# 4out_6A_TS_v0_1.net
KiCad netlist of a schematic drawn in EAGLE
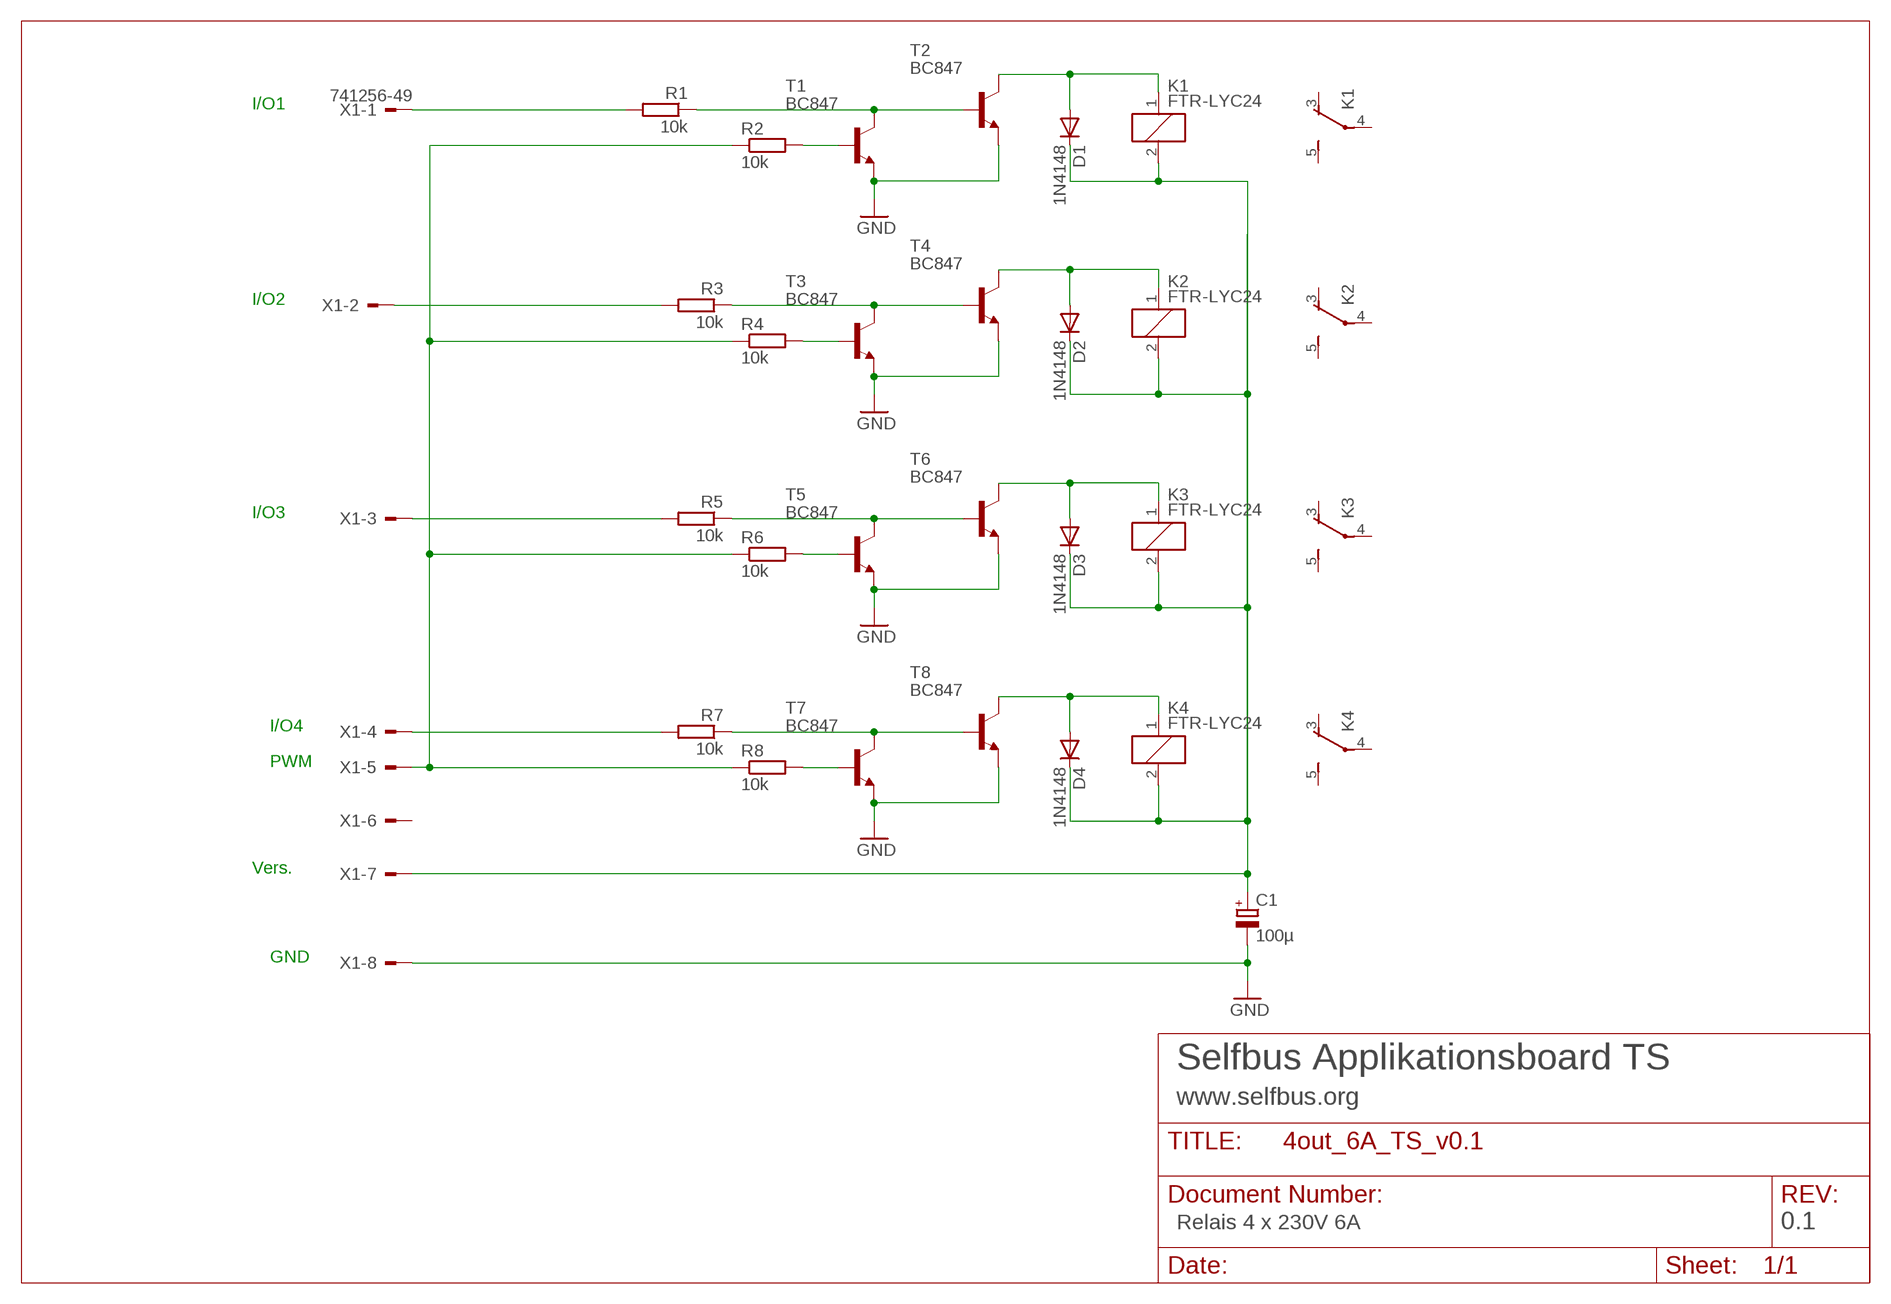
[diagram p0: schematic, sheet 1]

(export (version "E")
  (design (tool "Eeschema 10.0.6"))
  (components
    (comp (ref "C1")
      (value "100µ")
      (footprint "eagle-import:E2,5-6")
      (libsource (lib "eagle-import") (part "CPOL-EUE2.5-6"))
    )
    (comp (ref "D1")
      (value "1N4148")
      (footprint "eagle-import:MINIMELF")
      (libsource (lib "eagle-import") (part "DIODE-MINIMELF"))
    )
    (comp (ref "D2")
      (value "1N4148")
      (footprint "eagle-import:MINIMELF")
      (libsource (lib "eagle-import") (part "DIODE-MINIMELF"))
    )
    (comp (ref "D3")
      (value "1N4148")
      (footprint "eagle-import:MINIMELF")
      (libsource (lib "eagle-import") (part "DIODE-MINIMELF"))
    )
    (comp (ref "D4")
      (value "1N4148")
      (footprint "eagle-import:MINIMELF")
      (libsource (lib "eagle-import") (part "DIODE-MINIMELF"))
    )
    (comp (ref "K1")
      (value "FTR-LYC24")
      (footprint "eagle-import:FTR-LYC")
      (libsource (lib "eagle-import") (part "FTR-LYC24"))
    )
    (comp (ref "K2")
      (value "FTR-LYC24")
      (footprint "eagle-import:FTR-LYC")
      (libsource (lib "eagle-import") (part "FTR-LYC24"))
    )
    (comp (ref "K3")
      (value "FTR-LYC24")
      (footprint "eagle-import:FTR-LYC")
      (libsource (lib "eagle-import") (part "FTR-LYC24"))
    )
    (comp (ref "K4")
      (value "FTR-LYC24")
      (footprint "eagle-import:FTR-LYC")
      (libsource (lib "eagle-import") (part "FTR-LYC24"))
    )
    (comp (ref "R1")
      (value "10k")
      (footprint "eagle-import:M1206")
      (libsource (lib "eagle-import") (part "R-EU_M1206"))
    )
    (comp (ref "R2")
      (value "10k")
      (footprint "eagle-import:M1206")
      (libsource (lib "eagle-import") (part "R-EU_M1206"))
    )
    (comp (ref "R3")
      (value "10k")
      (footprint "eagle-import:M1206")
      (libsource (lib "eagle-import") (part "R-EU_M1206"))
    )
    (comp (ref "R4")
      (value "10k")
      (footprint "eagle-import:M1206")
      (libsource (lib "eagle-import") (part "R-EU_M1206"))
    )
    (comp (ref "R5")
      (value "10k")
      (footprint "eagle-import:M1206")
      (libsource (lib "eagle-import") (part "R-EU_M1206"))
    )
    (comp (ref "R6")
      (value "10k")
      (footprint "eagle-import:M1206")
      (libsource (lib "eagle-import") (part "R-EU_M1206"))
    )
    (comp (ref "R7")
      (value "10k")
      (footprint "eagle-import:M1206")
      (libsource (lib "eagle-import") (part "R-EU_M1206"))
    )
    (comp (ref "R8")
      (value "10k")
      (footprint "eagle-import:M1206")
      (libsource (lib "eagle-import") (part "R-EU_M1206"))
    )
    (comp (ref "T1")
      (value "BC847")
      (footprint "eagle-import:SOT23")
      (libsource (lib "eagle-import") (part "BC847"))
    )
    (comp (ref "T2")
      (value "BC847")
      (footprint "eagle-import:SOT23")
      (libsource (lib "eagle-import") (part "BC847"))
    )
    (comp (ref "T3")
      (value "BC847")
      (footprint "eagle-import:SOT23")
      (libsource (lib "eagle-import") (part "BC847"))
    )
    (comp (ref "T4")
      (value "BC847")
      (footprint "eagle-import:SOT23")
      (libsource (lib "eagle-import") (part "BC847"))
    )
    (comp (ref "T5")
      (value "BC847")
      (footprint "eagle-import:SOT23")
      (libsource (lib "eagle-import") (part "BC847"))
    )
    (comp (ref "T6")
      (value "BC847")
      (footprint "eagle-import:SOT23")
      (libsource (lib "eagle-import") (part "BC847"))
    )
    (comp (ref "T7")
      (value "BC847")
      (footprint "eagle-import:SOT23")
      (libsource (lib "eagle-import") (part "BC847"))
    )
    (comp (ref "T8")
      (value "BC847")
      (footprint "eagle-import:SOT23")
      (libsource (lib "eagle-import") (part "BC847"))
    )
    (comp (ref "X1")
      (value "741256-49")
      (footprint "eagle-import:741256-49")
      (libsource (lib "eagle-import") (part "741256-49"))
    )
  )
  (nets
    (net (code "1") (name "GND") (class "Default")
      (node (ref "C1") (pin "-") (pinfunction "-_-") (pintype "passive"))
      (node (ref "T1") (pin "2") (pinfunction "E_2") (pintype "passive"))
      (node (ref "T2") (pin "2") (pinfunction "E_2") (pintype "passive"))
      (node (ref "T3") (pin "2") (pinfunction "E_2") (pintype "passive"))
      (node (ref "T4") (pin "2") (pinfunction "E_2") (pintype "passive"))
      (node (ref "T5") (pin "2") (pinfunction "E_2") (pintype "passive"))
      (node (ref "T6") (pin "2") (pinfunction "E_2") (pintype "passive"))
      (node (ref "T7") (pin "2") (pinfunction "E_2") (pintype "passive"))
      (node (ref "T8") (pin "2") (pinfunction "E_2") (pintype "passive"))
      (node (ref "X1") (pin "8") (pinfunction "KL_8") (pintype "passive"))
    )
    (net (code "2") (name "Net-(T1-B)") (class "Default")
      (node (ref "R2") (pin "2") (pinfunction "2_2") (pintype "passive"))
      (node (ref "T1") (pin "1") (pinfunction "B_1") (pintype "passive"))
    )
    (net (code "3") (name "Net-(T1-C)") (class "Default")
      (node (ref "R1") (pin "1") (pinfunction "1_1") (pintype "passive"))
      (node (ref "T1") (pin "3") (pinfunction "C_3") (pintype "passive"))
      (node (ref "T2") (pin "1") (pinfunction "B_1") (pintype "passive"))
    )
    (net (code "4") (name "Net-(T2-C)") (class "Default")
      (node (ref "D1") (pin "A") (pinfunction "A_A") (pintype "passive"))
      (node (ref "K1") (pin "1") (pinfunction "1_1") (pintype "passive"))
      (node (ref "T2") (pin "3") (pinfunction "C_3") (pintype "passive"))
    )
    (net (code "5") (name "Net-(T3-B)") (class "Default")
      (node (ref "R4") (pin "2") (pinfunction "2_2") (pintype "passive"))
      (node (ref "T3") (pin "1") (pinfunction "B_1") (pintype "passive"))
    )
    (net (code "6") (name "Net-(T3-C)") (class "Default")
      (node (ref "R3") (pin "1") (pinfunction "1_1") (pintype "passive"))
      (node (ref "T3") (pin "3") (pinfunction "C_3") (pintype "passive"))
      (node (ref "T4") (pin "1") (pinfunction "B_1") (pintype "passive"))
    )
    (net (code "7") (name "Net-(T4-C)") (class "Default")
      (node (ref "D2") (pin "A") (pinfunction "A_A") (pintype "passive"))
      (node (ref "K2") (pin "1") (pinfunction "1_1") (pintype "passive"))
      (node (ref "T4") (pin "3") (pinfunction "C_3") (pintype "passive"))
    )
    (net (code "8") (name "Net-(T5-B)") (class "Default")
      (node (ref "R6") (pin "2") (pinfunction "2_2") (pintype "passive"))
      (node (ref "T5") (pin "1") (pinfunction "B_1") (pintype "passive"))
    )
    (net (code "9") (name "Net-(T5-C)") (class "Default")
      (node (ref "R5") (pin "1") (pinfunction "1_1") (pintype "passive"))
      (node (ref "T5") (pin "3") (pinfunction "C_3") (pintype "passive"))
      (node (ref "T6") (pin "1") (pinfunction "B_1") (pintype "passive"))
    )
    (net (code "10") (name "Net-(T6-C)") (class "Default")
      (node (ref "D3") (pin "A") (pinfunction "A_A") (pintype "passive"))
      (node (ref "K3") (pin "1") (pinfunction "1_1") (pintype "passive"))
      (node (ref "T6") (pin "3") (pinfunction "C_3") (pintype "passive"))
    )
    (net (code "11") (name "Net-(T7-B)") (class "Default")
      (node (ref "R8") (pin "2") (pinfunction "2_2") (pintype "passive"))
      (node (ref "T7") (pin "1") (pinfunction "B_1") (pintype "passive"))
    )
    (net (code "12") (name "Net-(T7-C)") (class "Default")
      (node (ref "R7") (pin "1") (pinfunction "1_1") (pintype "passive"))
      (node (ref "T7") (pin "3") (pinfunction "C_3") (pintype "passive"))
      (node (ref "T8") (pin "1") (pinfunction "B_1") (pintype "passive"))
    )
    (net (code "13") (name "Net-(T8-C)") (class "Default")
      (node (ref "D4") (pin "A") (pinfunction "A_A") (pintype "passive"))
      (node (ref "K4") (pin "1") (pinfunction "1_1") (pintype "passive"))
      (node (ref "T8") (pin "3") (pinfunction "C_3") (pintype "passive"))
    )
    (net (code "14") (name "Net-(X1A-KL)") (class "Default")
      (node (ref "R1") (pin "2") (pinfunction "2_2") (pintype "passive"))
      (node (ref "X1") (pin "1") (pinfunction "KL_1") (pintype "passive"))
    )
    (net (code "15") (name "Net-(X1B-KL)") (class "Default")
      (node (ref "R3") (pin "2") (pinfunction "2_2") (pintype "passive"))
      (node (ref "X1") (pin "2") (pinfunction "KL_2") (pintype "passive"))
    )
    (net (code "16") (name "Net-(X1C-KL)") (class "Default")
      (node (ref "R5") (pin "2") (pinfunction "2_2") (pintype "passive"))
      (node (ref "X1") (pin "3") (pinfunction "KL_3") (pintype "passive"))
    )
    (net (code "17") (name "Net-(X1D-KL)") (class "Default")
      (node (ref "R7") (pin "2") (pinfunction "2_2") (pintype "passive"))
      (node (ref "X1") (pin "4") (pinfunction "KL_4") (pintype "passive"))
    )
    (net (code "18") (name "Net-(X1E-KL)") (class "Default")
      (node (ref "R2") (pin "1") (pinfunction "1_1") (pintype "passive"))
      (node (ref "R4") (pin "1") (pinfunction "1_1") (pintype "passive"))
      (node (ref "R6") (pin "1") (pinfunction "1_1") (pintype "passive"))
      (node (ref "R8") (pin "1") (pinfunction "1_1") (pintype "passive"))
      (node (ref "X1") (pin "5") (pinfunction "KL_5") (pintype "passive"))
    )
    (net (code "19") (name "Net-(X1G-KL)") (class "Default")
      (node (ref "C1") (pin "+") (pinfunction "+_+") (pintype "passive"))
      (node (ref "D1") (pin "C") (pinfunction "C_C") (pintype "passive"))
      (node (ref "D2") (pin "C") (pinfunction "C_C") (pintype "passive"))
      (node (ref "D3") (pin "C") (pinfunction "C_C") (pintype "passive"))
      (node (ref "D4") (pin "C") (pinfunction "C_C") (pintype "passive"))
      (node (ref "K1") (pin "2") (pinfunction "2_2") (pintype "passive"))
      (node (ref "K2") (pin "2") (pinfunction "2_2") (pintype "passive"))
      (node (ref "K3") (pin "2") (pinfunction "2_2") (pintype "passive"))
      (node (ref "K4") (pin "2") (pinfunction "2_2") (pintype "passive"))
      (node (ref "X1") (pin "7") (pinfunction "KL_7") (pintype "passive"))
    )
    (net (code "20") (name "unconnected-(K1A-O-Pad3)") (class "Default")
      (node (ref "K1") (pin "3") (pinfunction "O_3") (pintype "passive"))
    )
    (net (code "21") (name "unconnected-(K1A-P-Pad4)") (class "Default")
      (node (ref "K1") (pin "4") (pinfunction "P_4") (pintype "passive"))
    )
    (net (code "22") (name "unconnected-(K1A-S-Pad5)") (class "Default")
      (node (ref "K1") (pin "5") (pinfunction "S_5") (pintype "passive"))
    )
    (net (code "23") (name "unconnected-(K2A-O-Pad3)") (class "Default")
      (node (ref "K2") (pin "3") (pinfunction "O_3") (pintype "passive"))
    )
    (net (code "24") (name "unconnected-(K2A-P-Pad4)") (class "Default")
      (node (ref "K2") (pin "4") (pinfunction "P_4") (pintype "passive"))
    )
    (net (code "25") (name "unconnected-(K2A-S-Pad5)") (class "Default")
      (node (ref "K2") (pin "5") (pinfunction "S_5") (pintype "passive"))
    )
    (net (code "26") (name "unconnected-(K3A-O-Pad3)") (class "Default")
      (node (ref "K3") (pin "3") (pinfunction "O_3") (pintype "passive"))
    )
    (net (code "27") (name "unconnected-(K3A-P-Pad4)") (class "Default")
      (node (ref "K3") (pin "4") (pinfunction "P_4") (pintype "passive"))
    )
    (net (code "28") (name "unconnected-(K3A-S-Pad5)") (class "Default")
      (node (ref "K3") (pin "5") (pinfunction "S_5") (pintype "passive"))
    )
    (net (code "29") (name "unconnected-(K4A-O-Pad3)") (class "Default")
      (node (ref "K4") (pin "3") (pinfunction "O_3") (pintype "passive"))
    )
    (net (code "30") (name "unconnected-(K4A-P-Pad4)") (class "Default")
      (node (ref "K4") (pin "4") (pinfunction "P_4") (pintype "passive"))
    )
    (net (code "31") (name "unconnected-(K4A-S-Pad5)") (class "Default")
      (node (ref "K4") (pin "5") (pinfunction "S_5") (pintype "passive"))
    )
    (net (code "32") (name "unconnected-(X1F-KL-Pad6)") (class "Default")
      (node (ref "X1") (pin "6") (pinfunction "KL_6") (pintype "passive"))
    )
  )
)
